# ledKjoleribbeKort.net
KiCad netlist of a schematic drawn in Altium Designer
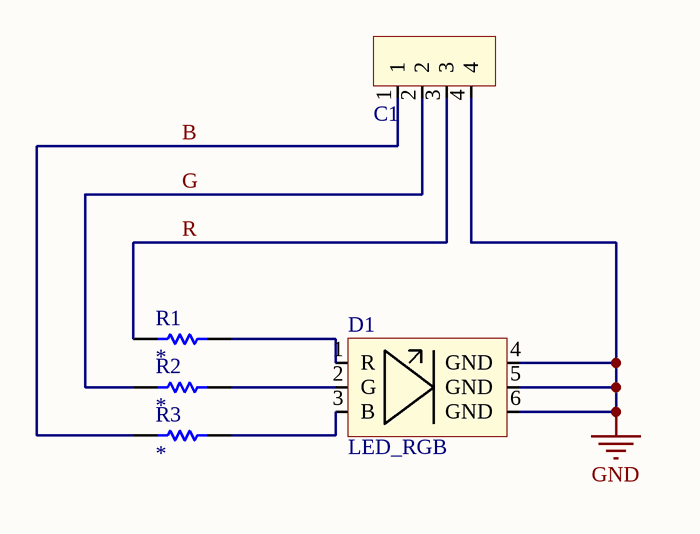
[diagram p0: ledKjoleribbeKort.SchDoc]

(export (version "E")
  (design (tool "Eeschema 10.0.6"))
  (components
    (comp (ref "C1") (value "GX10-4") (footprint "GX16-4") (libsource (lib "connectors") (part "GX10-4")))
    (comp (ref "D1") (value "LED_RGB") (footprint "LED_RGB_3W") (libsource (lib "diodes") (part "LED_RGB")))
    (comp (ref "R1")
      (value "RESISTOR")
      (footprint "EFFECT_RESISTOR_5W")
      (fields (field (name "RESISTANCE") "*"))
      (libsource (lib "resistors") (part "RESISTOR"))
    )
    (comp (ref "R2")
      (value "RESISTOR")
      (footprint "EFFECT_RESISTOR_5W")
      (fields (field (name "RESISTANCE") "*"))
      (libsource (lib "resistors") (part "RESISTOR"))
    )
    (comp (ref "R3")
      (value "RESISTOR")
      (footprint "EFFECT_RESISTOR_5W")
      (fields (field (name "RESISTANCE") "*"))
      (libsource (lib "resistors") (part "RESISTOR"))
    )
  )
  (nets
    (net (code "1") (name "/B") (class "Default")
      (node (ref "C1") (pin "1") (pinfunction "1_1") (pintype "passive"))
      (node (ref "R3") (pin "1") (pinfunction "1_1") (pintype "passive"))
    )
    (net (code "2") (name "/G") (class "Default")
      (node (ref "C1") (pin "2") (pinfunction "2_2") (pintype "passive"))
      (node (ref "R2") (pin "1") (pinfunction "1_1") (pintype "passive"))
    )
    (net (code "3") (name "/R") (class "Default")
      (node (ref "C1") (pin "3") (pinfunction "3_3") (pintype "passive"))
      (node (ref "R1") (pin "1") (pinfunction "1_1") (pintype "passive"))
    )
    (net (code "4") (name "GND") (class "Default")
      (node (ref "C1") (pin "4") (pinfunction "4_4") (pintype "passive"))
      (node (ref "D1") (pin "4") (pinfunction "GND_4") (pintype "passive"))
      (node (ref "D1") (pin "5") (pinfunction "GND_5") (pintype "passive"))
      (node (ref "D1") (pin "6") (pinfunction "GND_6") (pintype "passive"))
    )
    (net (code "5") (name "Net-(D1-B)") (class "Default")
      (node (ref "D1") (pin "3") (pinfunction "B_3") (pintype "passive"))
      (node (ref "R3") (pin "2") (pinfunction "2_2") (pintype "passive"))
    )
    (net (code "6") (name "Net-(D1-G)") (class "Default")
      (node (ref "D1") (pin "2") (pinfunction "G_2") (pintype "passive"))
      (node (ref "R2") (pin "2") (pinfunction "2_2") (pintype "passive"))
    )
    (net (code "7") (name "Net-(D1-R)") (class "Default")
      (node (ref "D1") (pin "1") (pinfunction "R_1") (pintype "passive"))
      (node (ref "R1") (pin "2") (pinfunction "2_2") (pintype "passive"))
    )
  )
)
